# mini_shirasu.net
KiCad netlist of a schematic drawn in EAGLE
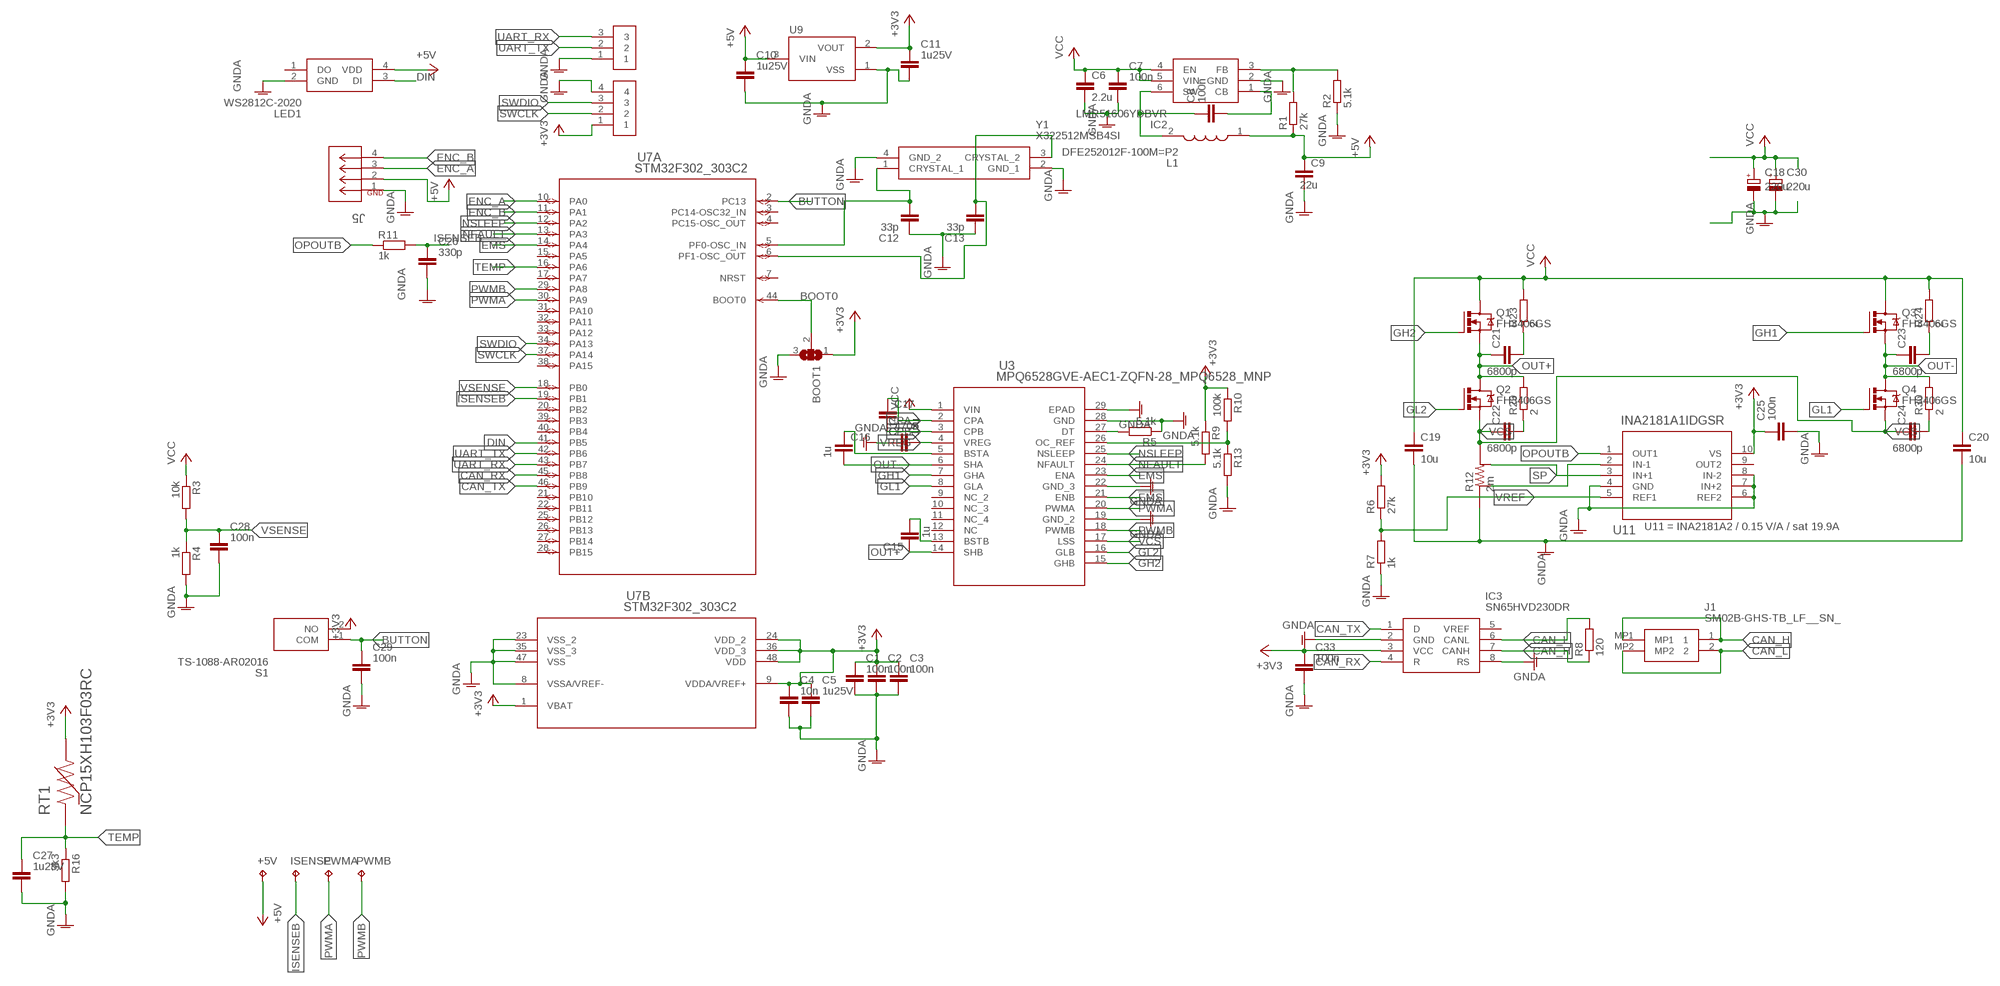
[diagram p0: schematic, sheet 1, part 1 of 2]
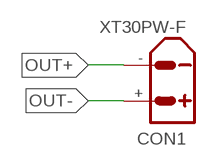
[diagram p1: schematic, sheet 1, part 2 of 2]

(export (version "E")
  (design (tool "Eeschema 10.0.6"))
  (components
    (comp (ref "+5V")
      (value "TPB1,27")
      (footprint "eagle-import:B1,27")
      (libsource (lib "eagle-import") (part "TPB1,27"))
    )
    (comp (ref "BOOT1")
      (value "SJ2W")
      (footprint "eagle-import:SJ_2")
      (libsource (lib "eagle-import") (part "SJ2W"))
    )
    (comp (ref "C1")
      (value "100n")
      (footprint "eagle-import:CAPC1005X60")
      (libsource (lib "eagle-import") (part "CCHIP-0402(1005-METRIC)_"))
    )
    (comp (ref "C2")
      (value "100n")
      (footprint "eagle-import:CAPC1005X60")
      (libsource (lib "eagle-import") (part "CCHIP-0402(1005-METRIC)_"))
    )
    (comp (ref "C3")
      (value "100n")
      (footprint "eagle-import:CAPC1005X60")
      (libsource (lib "eagle-import") (part "CCHIP-0402(1005-METRIC)_"))
    )
    (comp (ref "C4")
      (value "10n")
      (footprint "eagle-import:CAPC1005X60")
      (libsource (lib "eagle-import") (part "CCHIP-0402(1005-METRIC)_"))
    )
    (comp (ref "C5")
      (value "1u25V")
      (footprint "eagle-import:CAPC1005X60")
      (libsource (lib "eagle-import") (part "CCHIP-0402(1005-METRIC)_"))
    )
    (comp (ref "C6")
      (value "2.2u")
      (footprint "eagle-import:C0805")
      (libsource (lib "eagle-import") (part "C-EUC0805"))
    )
    (comp (ref "C7")
      (value "100n")
      (footprint "eagle-import:CAPC1005X60")
      (libsource (lib "eagle-import") (part "CCHIP-0402(1005-METRIC)_"))
    )
    (comp (ref "C8")
      (value "100n")
      (footprint "eagle-import:CAPC1005X60")
      (libsource (lib "eagle-import") (part "CCHIP-0402(1005-METRIC)_"))
    )
    (comp (ref "C9")
      (value "22u")
      (footprint "eagle-import:C0805")
      (libsource (lib "eagle-import") (part "C-EUC0805"))
    )
    (comp (ref "C10")
      (value "1u25V")
      (footprint "eagle-import:CAPC1005X60")
      (libsource (lib "eagle-import") (part "CCHIP-0402(1005-METRIC)_"))
    )
    (comp (ref "C11")
      (value "1u25V")
      (footprint "eagle-import:CAPC1005X60")
      (libsource (lib "eagle-import") (part "CCHIP-0402(1005-METRIC)_"))
    )
    (comp (ref "C12")
      (value "33p")
      (footprint "eagle-import:CAPC1005X60")
      (libsource (lib "eagle-import") (part "CCHIP-0402(1005-METRIC)_"))
    )
    (comp (ref "C13")
      (value "33p")
      (footprint "eagle-import:CAPC1005X60")
      (libsource (lib "eagle-import") (part "CCHIP-0402(1005-METRIC)_"))
    )
    (comp (ref "C14")
      (value "10u")
      (footprint "eagle-import:C0805")
      (libsource (lib "eagle-import") (part "C-EUC0805"))
    )
    (comp (ref "C15")
      (value "1u")
      (footprint "eagle-import:C0603")
      (libsource (lib "eagle-import") (part "C-EUC0603"))
    )
    (comp (ref "C16")
      (value "1u")
      (footprint "eagle-import:C0603")
      (libsource (lib "eagle-import") (part "C-EUC0603"))
    )
    (comp (ref "C17")
      (value "470n")
      (footprint "eagle-import:C0805")
      (libsource (lib "eagle-import") (part "C-EUC0805"))
    )
    (comp (ref "C18")
      (value "220u")
      (footprint "eagle-import:CAPAE1030X1050N")
      (libsource (lib "eagle-import") (part "C-POLECAP-10.5MM_"))
    )
    (comp (ref "C19")
      (value "10u")
      (footprint "eagle-import:C0805")
      (libsource (lib "eagle-import") (part "C-EUC0805"))
    )
    (comp (ref "C20")
      (value "10u")
      (footprint "eagle-import:C0805")
      (libsource (lib "eagle-import") (part "C-EUC0805"))
    )
    (comp (ref "C21")
      (value "6800p")
      (footprint "eagle-import:C0603")
      (libsource (lib "eagle-import") (part "C-EUC0603"))
    )
    (comp (ref "C22")
      (value "6800p")
      (footprint "eagle-import:C0603")
      (libsource (lib "eagle-import") (part "C-EUC0603"))
    )
    (comp (ref "C23")
      (value "6800p")
      (footprint "eagle-import:C0603")
      (libsource (lib "eagle-import") (part "C-EUC0603"))
    )
    (comp (ref "C24")
      (value "6800p")
      (footprint "eagle-import:C0603")
      (libsource (lib "eagle-import") (part "C-EUC0603"))
    )
    (comp (ref "C25")
      (value "100n")
      (footprint "eagle-import:CAPC1005X60")
      (libsource (lib "eagle-import") (part "CCHIP-0402(1005-METRIC)_"))
    )
    (comp (ref "C26")
      (value "330p")
      (footprint "eagle-import:CAPC1005X60")
      (libsource (lib "eagle-import") (part "CCHIP-0402(1005-METRIC)_"))
    )
    (comp (ref "C27")
      (value "1u25V")
      (footprint "eagle-import:CAPC1005X60")
      (libsource (lib "eagle-import") (part "CCHIP-0402(1005-METRIC)_"))
    )
    (comp (ref "C28")
      (value "100n")
      (footprint "eagle-import:CAPC1005X60")
      (libsource (lib "eagle-import") (part "CCHIP-0402(1005-METRIC)_"))
    )
    (comp (ref "C29")
      (value "100n")
      (footprint "eagle-import:CAPC1005X60")
      (libsource (lib "eagle-import") (part "CCHIP-0402(1005-METRIC)_"))
    )
    (comp (ref "C30")
      (value "220u")
      (footprint "eagle-import:CAPAE1030X1050N")
      (libsource (lib "eagle-import") (part "C-POLECAP-10.5MM_"))
    )
    (comp (ref "C33")
      (value "100n")
      (footprint "eagle-import:CAPC1005X60")
      (libsource (lib "eagle-import") (part "CCHIP-0402(1005-METRIC)_"))
    )
    (comp (ref "CON1")
      (value "XT30PW-F")
      (footprint "eagle-import:XT30PW-F")
      (libsource (lib "eagle-import") (part "XT30PW-F"))
    )
    (comp (ref "IC2")
      (value "LMR51606YDBVR")
      (footprint "eagle-import:SOT95P280X145-6N")
      (fields (field (name "MOUSER_PART_NUMBER") "595-LMR51606YDBVR"))
      (libsource (lib "eagle-import") (part "LMR51606YDBVR"))
    )
    (comp (ref "IC3")
      (value "SN65HVD230DR")
      (footprint "eagle-import:SOT127P600X175-8N")
      (fields (field (name "MOUSER_PART_NUMBER") "595-SN65HVD230DR"))
      (libsource (lib "eagle-import") (part "SN65HVD230DR"))
    )
    (comp (ref "ISENSE")
      (value "TPB1,27")
      (footprint "eagle-import:B1,27")
      (libsource (lib "eagle-import") (part "TPB1,27"))
    )
    (comp (ref "J1")
      (value "SM02B-GHS-TB_LF__SN_")
      (footprint "eagle-import:SM02BGHSTBLFSN")
      (fields (field (name "MANUFACTURER") "JST") (field (name "MPN") "SM02B-GHS-TB(LF)(SN)"))
      (libsource (lib "eagle-import") (part "SM02B-GHS-TB_LF__SN_"))
    )
    (comp (ref "J5")
      (value "EP2.5-4-SIDE")
      (footprint "eagle-import:CONN4_1744426-4")
      (fields (field (name "MANUFACTURER_PART_NUMBER") "17444264"))
      (libsource (lib "eagle-import") (part "EP2.5-4-SIDE"))
    )
    (comp (ref "L1")
      (value "DFE252012F-100M=P2")
      (footprint "eagle-import:DFE2HCAH1R0MJ0L")
      (fields (field (name "MOUSER_PART_NUMBER") "81-DFE252012F-100MP2"))
      (libsource (lib "eagle-import") (part "DFE252012F-100M=P2"))
    )
    (comp (ref "LED1")
      (value "WS2812C-2020")
      (footprint "eagle-import:WS2812C2020")
      (libsource (lib "eagle-import") (part "WS2812C-2020"))
    )
    (comp (ref "PWMA")
      (value "TPB1,27")
      (footprint "eagle-import:B1,27")
      (libsource (lib "eagle-import") (part "TPB1,27"))
    )
    (comp (ref "PWMB")
      (value "TPB1,27")
      (footprint "eagle-import:B1,27")
      (libsource (lib "eagle-import") (part "TPB1,27"))
    )
    (comp (ref "Q1")
      (value "FH3406GS")
      (footprint "eagle-import:DFN-8-5X6-FH3406GS")
      (libsource (lib "eagle-import") (part "FH3406GS"))
    )
    (comp (ref "Q2")
      (value "FH3406GS")
      (footprint "eagle-import:DFN-8-5X6-FH3406GS")
      (libsource (lib "eagle-import") (part "FH3406GS"))
    )
    (comp (ref "Q3")
      (value "FH3406GS")
      (footprint "eagle-import:DFN-8-5X6-FH3406GS")
      (libsource (lib "eagle-import") (part "FH3406GS"))
    )
    (comp (ref "Q4")
      (value "FH3406GS")
      (footprint "eagle-import:DFN-8-5X6-FH3406GS")
      (libsource (lib "eagle-import") (part "FH3406GS"))
    )
    (comp (ref "R1")
      (value "27k")
      (footprint "eagle-import:R0402")
      (libsource (lib "eagle-import") (part "R-EU_R0402"))
    )
    (comp (ref "R2")
      (value "5.1k")
      (footprint "eagle-import:R0402")
      (libsource (lib "eagle-import") (part "R-EU_R0402"))
    )
    (comp (ref "R3")
      (value "10k")
      (footprint "eagle-import:R0402")
      (libsource (lib "eagle-import") (part "R-EU_R0402"))
    )
    (comp (ref "R4")
      (value "1k")
      (footprint "eagle-import:R0402")
      (libsource (lib "eagle-import") (part "R-EU_R0402"))
    )
    (comp (ref "R5")
      (value "5.1k")
      (footprint "eagle-import:R0402")
      (libsource (lib "eagle-import") (part "R-EU_R0402"))
    )
    (comp (ref "R6")
      (value "27k")
      (footprint "eagle-import:R0402")
      (libsource (lib "eagle-import") (part "R-EU_R0402"))
    )
    (comp (ref "R7")
      (value "1k")
      (footprint "eagle-import:R0402")
      (libsource (lib "eagle-import") (part "R-EU_R0402"))
    )
    (comp (ref "R8")
      (value "120")
      (footprint "eagle-import:R0603")
      (libsource (lib "eagle-import") (part "R-EU_R0603"))
    )
    (comp (ref "R9")
      (value "5.1k")
      (footprint "eagle-import:R0402")
      (libsource (lib "eagle-import") (part "R-EU_R0402"))
    )
    (comp (ref "R10")
      (value "100k")
      (footprint "eagle-import:R0402")
      (libsource (lib "eagle-import") (part "R-EU_R0402"))
    )
    (comp (ref "R11")
      (value "1k")
      (footprint "eagle-import:R0402")
      (libsource (lib "eagle-import") (part "R-EU_R0402"))
    )
    (comp (ref "R12")
      (value "2m")
      (footprint "eagle-import:2512-4PAD")
      (libsource (lib "eagle-import") (part "R2512"))
    )
    (comp (ref "R13")
      (value "5.1k")
      (footprint "eagle-import:R0402")
      (libsource (lib "eagle-import") (part "R-EU_R0402"))
    )
    (comp (ref "R16")
      (value "3k3")
      (footprint "eagle-import:R0402")
      (libsource (lib "eagle-import") (part "R-EU_R0402"))
    )
    (comp (ref "R23")
      (value "2")
      (footprint "eagle-import:R0603")
      (libsource (lib "eagle-import") (part "R-EU_R0603"))
    )
    (comp (ref "R24")
      (value "2")
      (footprint "eagle-import:R0603")
      (libsource (lib "eagle-import") (part "R-EU_R0603"))
    )
    (comp (ref "R29")
      (value "2")
      (footprint "eagle-import:R0603")
      (libsource (lib "eagle-import") (part "R-EU_R0603"))
    )
    (comp (ref "R30")
      (value "2")
      (footprint "eagle-import:R0603")
      (libsource (lib "eagle-import") (part "R-EU_R0603"))
    )
    (comp (ref "RT1")
      (value "NCP15XH103F03RC")
      (footprint "eagle-import:THRMC1005X55N")
      (fields (field (name "MF") "Murata"))
      (libsource (lib "eagle-import") (part "NCP15XH103F03RC"))
    )
    (comp (ref "S1")
      (value "TS-1088-AR02016")
      (footprint "eagle-import:TS1088AR02016")
      (libsource (lib "eagle-import") (part "TS-1088-AR02016"))
    )
    (comp (ref "U$1")
      (value "PIN_HEADERPIN_HEADER")
      (footprint "eagle-import:PIN_HEADER")
      (libsource (lib "eagle-import") (part "PIN_HEADERPIN_HEADER"))
    )
    (comp (ref "U$2")
      (value "3PIN_HEADER")
      (footprint "eagle-import:3PIN_HEADER")
      (libsource (lib "eagle-import") (part "3PIN_HEADER"))
    )
    (comp (ref "U3")
      (value "MPQ6528GVE-AEC1-ZQFN-28_MPQ6528_MNP")
      (footprint "eagle-import:QFN-28_MPQ6528_MNP")
      (fields
        (field (name "MANUFACTURER_PART_NUMBER") "MPQ6528GVE-AEC1-Z")
        (field (name "COPYRIGHT") "Copyright (C) 2026 Ultra Librarian. All rights reserved.")
      )
      (libsource (lib "eagle-import") (part "MPQ6528GVE-AEC1-ZQFN-28_MPQ6528_MNP"))
    )
    (comp (ref "U7")
      (value "STM32F302_303C2")
      (footprint "eagle-import:LQFP48-7X7MM")
      (fields (field (name "COPYRIGHT") "Copyright (C) 2016 Accelerated Designs. All rights reserved"))
      (libsource (lib "eagle-import") (part "STM32F302_303C2"))
    )
    (comp (ref "U9")
      (value "XC6206")
      (footprint "eagle-import:SOT95P240X110-3")
      (libsource (lib "eagle-import") (part "XC6206"))
    )
    (comp (ref "U11")
      (value "INA2181A1IDGSR")
      (footprint "eagle-import:DGS10")
      (fields
        (field (name "MANUFACTURER_PART_NUMBER") "INA2181A2IDGSR")
        (field (name "COPYRIGHT") "Copyright (C) 2018 Accelerated Designs. All rights reserved")
      )
      (libsource (lib "eagle-import") (part "INA2181A1IDGSR"))
    )
    (comp (ref "Y1")
      (value "X322512MSB4SI")
      (footprint "eagle-import:X322512MSB4SI")
      (libsource (lib "eagle-import") (part "X322512MSB4SI"))
    )
  )
  (nets
    (net (code "1") (name "+3V3") (class "Default")
      (node (ref "BOOT1") (pin "1") (pinfunction "1_1") (pintype "passive"))
      (node (ref "C1") (pin "1") (pinfunction "1_1") (pintype "passive"))
      (node (ref "C11") (pin "1") (pinfunction "1_1") (pintype "passive"))
      (node (ref "C2") (pin "1") (pinfunction "1_1") (pintype "passive"))
      (node (ref "C25") (pin "1") (pinfunction "1_1") (pintype "passive"))
      (node (ref "C3") (pin "1") (pinfunction "1_1") (pintype "passive"))
      (node (ref "C33") (pin "1") (pinfunction "1_1") (pintype "passive"))
      (node (ref "C4") (pin "1") (pinfunction "1_1") (pintype "passive"))
      (node (ref "C5") (pin "1") (pinfunction "1_1") (pintype "passive"))
      (node (ref "IC3") (pin "3") (pinfunction "VCC_3") (pintype "bidirectional"))
      (node (ref "R10") (pin "1") (pinfunction "1_1") (pintype "passive"))
      (node (ref "R6") (pin "2") (pinfunction "2_2") (pintype "passive"))
      (node (ref "R9") (pin "1") (pinfunction "1_1") (pintype "passive"))
      (node (ref "RT1") (pin "2") (pinfunction "2_2") (pintype "passive"))
      (node (ref "S1") (pin "2") (pinfunction "NO_2") (pintype "bidirectional"))
      (node (ref "U$1") (pin "1") (pinfunction "1_1") (pintype "bidirectional"))
      (node (ref "U11") (pin "10") (pinfunction "VS_10") (pintype "power_in"))
      (node (ref "U7") (pin "1") (pinfunction "VBAT_1") (pintype "power_in"))
      (node (ref "U7") (pin "24") (pinfunction "VDD_2_24") (pintype "power_in"))
      (node (ref "U7") (pin "36") (pinfunction "VDD_3_36") (pintype "power_in"))
      (node (ref "U7") (pin "48") (pinfunction "VDD_48") (pintype "power_in"))
      (node (ref "U7") (pin "9") (pinfunction "VDDA/VREF+_9") (pintype "power_in"))
      (node (ref "U9") (pin "2") (pinfunction "VOUT_2") (pintype "bidirectional"))
    )
    (net (code "2") (name "+5V") (class "Default")
      (node (ref "+5V") (pin "TP") (pinfunction "TP_TP") (pintype "input"))
      (node (ref "C10") (pin "1") (pinfunction "1_1") (pintype "passive"))
      (node (ref "C9") (pin "1") (pinfunction "1_1") (pintype "passive"))
      (node (ref "J5") (pin "2") (pinfunction "2_2") (pintype "passive"))
      (node (ref "L1") (pin "1") (pinfunction "1_1") (pintype "bidirectional"))
      (node (ref "LED1") (pin "4") (pinfunction "VDD_4") (pintype "bidirectional"))
      (node (ref "R1") (pin "1") (pinfunction "1_1") (pintype "passive"))
      (node (ref "U9") (pin "3") (pinfunction "VIN_3") (pintype "bidirectional"))
    )
    (net (code "3") (name "/BOOT0") (class "Default")
      (node (ref "BOOT1") (pin "2") (pinfunction "2_2") (pintype "passive"))
      (node (ref "U7") (pin "44") (pinfunction "BOOT0_44") (pintype "input"))
    )
    (net (code "4") (name "/~{EMS}") (class "Default")
      (node (ref "U3") (pin "21") (pinfunction "ENB_21") (pintype "power_in"))
      (node (ref "U3") (pin "23") (pinfunction "ENA_23") (pintype "passive"))
      (node (ref "U7") (pin "14") (pinfunction "PA4_14") (pintype "bidirectional"))
    )
    (net (code "5") (name "BUTTON") (class "Default")
      (node (ref "C29") (pin "1") (pinfunction "1_1") (pintype "passive"))
      (node (ref "S1") (pin "1") (pinfunction "COM_1") (pintype "bidirectional"))
      (node (ref "U7") (pin "2") (pinfunction "PC13_2") (pintype "bidirectional"))
    )
    (net (code "6") (name "CAN_H") (class "Default")
      (node (ref "IC3") (pin "7") (pinfunction "CANH_7") (pintype "bidirectional"))
      (node (ref "J1") (pin "1") (pinfunction "1_1") (pintype "bidirectional"))
      (node (ref "J1") (pin "MP1") (pinfunction "MP1_MP1") (pintype "bidirectional"))
      (node (ref "R8") (pin "1") (pinfunction "1_1") (pintype "passive"))
    )
    (net (code "7") (name "CAN_L") (class "Default")
      (node (ref "IC3") (pin "6") (pinfunction "CANL_6") (pintype "bidirectional"))
      (node (ref "J1") (pin "2") (pinfunction "2_2") (pintype "bidirectional"))
      (node (ref "J1") (pin "MP2") (pinfunction "MP2_MP2") (pintype "bidirectional"))
      (node (ref "R8") (pin "2") (pinfunction "2_2") (pintype "passive"))
    )
    (net (code "8") (name "CAN_RX") (class "Default")
      (node (ref "IC3") (pin "4") (pinfunction "R_4") (pintype "bidirectional"))
      (node (ref "U7") (pin "45") (pinfunction "PB8_45") (pintype "bidirectional"))
    )
    (net (code "9") (name "CAN_TX") (class "Default")
      (node (ref "IC3") (pin "1") (pinfunction "D_1") (pintype "bidirectional"))
      (node (ref "U7") (pin "46") (pinfunction "PB9_46") (pintype "bidirectional"))
    )
    (net (code "10") (name "CPA") (class "Default")
      (node (ref "C17") (pin "1") (pinfunction "1_1") (pintype "passive"))
      (node (ref "U3") (pin "2") (pinfunction "CPA_2") (pintype "passive"))
    )
    (net (code "11") (name "CPB") (class "Default")
      (node (ref "C17") (pin "2") (pinfunction "2_2") (pintype "passive"))
      (node (ref "U3") (pin "3") (pinfunction "CPB_3") (pintype "passive"))
    )
    (net (code "12") (name "DIN") (class "Default")
      (node (ref "LED1") (pin "3") (pinfunction "DI_3") (pintype "bidirectional"))
      (node (ref "U7") (pin "41") (pinfunction "PB5_41") (pintype "bidirectional"))
    )
    (net (code "13") (name "ENC_A") (class "Default")
      (node (ref "J5") (pin "3") (pinfunction "3_3") (pintype "passive"))
      (node (ref "U7") (pin "10") (pinfunction "PA0_10") (pintype "bidirectional"))
    )
    (net (code "14") (name "ENC_B") (class "Default")
      (node (ref "J5") (pin "4") (pinfunction "4_4") (pintype "passive"))
      (node (ref "U7") (pin "11") (pinfunction "PA1_11") (pintype "bidirectional"))
    )
    (net (code "15") (name "GH1") (class "Default")
      (node (ref "Q3") (pin "4") (pinfunction "G_4") (pintype "passive"))
      (node (ref "U3") (pin "7") (pinfunction "GHA_7") (pintype "passive"))
    )
    (net (code "16") (name "GH2") (class "Default")
      (node (ref "Q1") (pin "4") (pinfunction "G_4") (pintype "passive"))
      (node (ref "U3") (pin "15") (pinfunction "GHB_15") (pintype "passive"))
    )
    (net (code "17") (name "GL1") (class "Default")
      (node (ref "Q4") (pin "4") (pinfunction "G_4") (pintype "passive"))
      (node (ref "U3") (pin "8") (pinfunction "GLA_8") (pintype "passive"))
    )
    (net (code "18") (name "GL2") (class "Default")
      (node (ref "Q2") (pin "4") (pinfunction "G_4") (pintype "passive"))
      (node (ref "U3") (pin "16") (pinfunction "GLB_16") (pintype "passive"))
    )
    (net (code "19") (name "GNDA") (class "Default")
      (node (ref "BOOT1") (pin "3") (pinfunction "3_3") (pintype "passive"))
      (node (ref "C1") (pin "2") (pinfunction "2_2") (pintype "passive"))
      (node (ref "C10") (pin "2") (pinfunction "2_2") (pintype "passive"))
      (node (ref "C11") (pin "2") (pinfunction "2_2") (pintype "passive"))
      (node (ref "C12") (pin "1") (pinfunction "1_1") (pintype "passive"))
      (node (ref "C13") (pin "1") (pinfunction "1_1") (pintype "passive"))
      (node (ref "C14") (pin "1") (pinfunction "1_1") (pintype "passive"))
      (node (ref "C18") (pin "2") (pinfunction "-_2") (pintype "passive"))
      (node (ref "C19") (pin "2") (pinfunction "2_2") (pintype "passive"))
      (node (ref "C2") (pin "2") (pinfunction "2_2") (pintype "passive"))
      (node (ref "C20") (pin "2") (pinfunction "2_2") (pintype "passive"))
      (node (ref "C25") (pin "2") (pinfunction "2_2") (pintype "passive"))
      (node (ref "C26") (pin "2") (pinfunction "2_2") (pintype "passive"))
      (node (ref "C27") (pin "2") (pinfunction "2_2") (pintype "passive"))
      (node (ref "C28") (pin "2") (pinfunction "2_2") (pintype "passive"))
      (node (ref "C29") (pin "2") (pinfunction "2_2") (pintype "passive"))
      (node (ref "C3") (pin "2") (pinfunction "2_2") (pintype "passive"))
      (node (ref "C30") (pin "2") (pinfunction "-_2") (pintype "passive"))
      (node (ref "C33") (pin "2") (pinfunction "2_2") (pintype "passive"))
      (node (ref "C4") (pin "2") (pinfunction "2_2") (pintype "passive"))
      (node (ref "C5") (pin "2") (pinfunction "2_2") (pintype "passive"))
      (node (ref "C6") (pin "2") (pinfunction "2_2") (pintype "passive"))
      (node (ref "C7") (pin "2") (pinfunction "2_2") (pintype "passive"))
      (node (ref "C9") (pin "2") (pinfunction "2_2") (pintype "passive"))
      (node (ref "IC2") (pin "2") (pinfunction "GND_2") (pintype "bidirectional"))
      (node (ref "IC3") (pin "2") (pinfunction "GND_2") (pintype "bidirectional"))
      (node (ref "IC3") (pin "8") (pinfunction "RS_8") (pintype "bidirectional"))
      (node (ref "J5") (pin "1") (pinfunction "1_1") (pintype "passive"))
      (node (ref "LED1") (pin "2") (pinfunction "GND_2") (pintype "bidirectional"))
      (node (ref "R12") (pin "1") (pinfunction "1_1") (pintype "passive"))
      (node (ref "R12") (pin "2") (pinfunction "1_2") (pintype "passive"))
      (node (ref "R13") (pin "2") (pinfunction "2_2") (pintype "passive"))
      (node (ref "R16") (pin "2") (pinfunction "2_2") (pintype "passive"))
      (node (ref "R2") (pin "1") (pinfunction "1_1") (pintype "passive"))
      (node (ref "R4") (pin "2") (pinfunction "2_2") (pintype "passive"))
      (node (ref "R5") (pin "1") (pinfunction "1_1") (pintype "passive"))
      (node (ref "R7") (pin "1") (pinfunction "1_1") (pintype "passive"))
      (node (ref "U$1") (pin "4") (pinfunction "4_4") (pintype "bidirectional"))
      (node (ref "U$2") (pin "1") (pinfunction "1_1") (pintype "bidirectional"))
      (node (ref "U11") (pin "4") (pinfunction "GND_4") (pintype "power_in"))
      (node (ref "U11") (pin "6") (pinfunction "REF2_6") (pintype "input"))
      (node (ref "U11") (pin "7") (pinfunction "IN+2_7") (pintype "input"))
      (node (ref "U11") (pin "8") (pinfunction "IN-2_8") (pintype "input"))
      (node (ref "U3") (pin "19") (pinfunction "GND_2_19") (pintype "power_in"))
      (node (ref "U3") (pin "22") (pinfunction "GND_3_22") (pintype "passive"))
      (node (ref "U3") (pin "28") (pinfunction "GND_28") (pintype "power_in"))
      (node (ref "U3") (pin "29") (pinfunction "EPAD_29") (pintype "power_in"))
      (node (ref "U7") (pin "23") (pinfunction "VSS_2_23") (pintype "power_in"))
      (node (ref "U7") (pin "35") (pinfunction "VSS_3_35") (pintype "power_in"))
      (node (ref "U7") (pin "47") (pinfunction "VSS_47") (pintype "power_in"))
      (node (ref "U7") (pin "8") (pinfunction "VSSA/VREF-_8") (pintype "power_in"))
      (node (ref "U9") (pin "1") (pinfunction "VSS_1") (pintype "bidirectional"))
      (node (ref "Y1") (pin "2") (pinfunction "GND_1_2") (pintype "bidirectional"))
      (node (ref "Y1") (pin "4") (pinfunction "GND_2_4") (pintype "bidirectional"))
    )
    (net (code "20") (name "ISENSEB") (class "Default")
      (node (ref "C26") (pin "1") (pinfunction "1_1") (pintype "passive"))
      (node (ref "ISENSE") (pin "TP") (pinfunction "TP_TP") (pintype "input"))
      (node (ref "R11") (pin "2") (pinfunction "2_2") (pintype "passive"))
      (node (ref "U7") (pin "19") (pinfunction "PB1_19") (pintype "bidirectional"))
    )
    (net (code "21") (name "NFAULT") (class "Default")
      (node (ref "R9") (pin "2") (pinfunction "2_2") (pintype "passive"))
      (node (ref "U3") (pin "24") (pinfunction "NFAULT_24") (pintype "output"))
      (node (ref "U7") (pin "13") (pinfunction "PA3_13") (pintype "bidirectional"))
    )
    (net (code "22") (name "NSLEEP") (class "Default")
      (node (ref "U3") (pin "25") (pinfunction "NSLEEP_25") (pintype "input"))
      (node (ref "U7") (pin "12") (pinfunction "PA2_12") (pintype "bidirectional"))
    )
    (net (code "23") (name "Net-(C21-Pad2)") (class "Default")
      (node (ref "C21") (pin "2") (pinfunction "2_2") (pintype "passive"))
      (node (ref "R23") (pin "1") (pinfunction "1_1") (pintype "passive"))
    )
    (net (code "24") (name "Net-(C22-Pad2)") (class "Default")
      (node (ref "C22") (pin "2") (pinfunction "2_2") (pintype "passive"))
      (node (ref "R29") (pin "1") (pinfunction "1_1") (pintype "passive"))
    )
    (net (code "25") (name "Net-(C23-Pad2)") (class "Default")
      (node (ref "C23") (pin "2") (pinfunction "2_2") (pintype "passive"))
      (node (ref "R24") (pin "1") (pinfunction "1_1") (pintype "passive"))
    )
    (net (code "26") (name "Net-(C24-Pad2)") (class "Default")
      (node (ref "C24") (pin "2") (pinfunction "2_2") (pintype "passive"))
      (node (ref "R30") (pin "1") (pinfunction "1_1") (pintype "passive"))
    )
    (net (code "27") (name "Net-(IC2-CB)") (class "Default")
      (node (ref "C8") (pin "2") (pinfunction "2_2") (pintype "passive"))
      (node (ref "IC2") (pin "1") (pinfunction "CB_1") (pintype "bidirectional"))
    )
    (net (code "28") (name "Net-(IC2-FB)") (class "Default")
      (node (ref "IC2") (pin "3") (pinfunction "FB_3") (pintype "bidirectional"))
      (node (ref "R1") (pin "2") (pinfunction "2_2") (pintype "passive"))
      (node (ref "R2") (pin "2") (pinfunction "2_2") (pintype "passive"))
    )
    (net (code "29") (name "Net-(IC2-SW)") (class "Default")
      (node (ref "C8") (pin "1") (pinfunction "1_1") (pintype "passive"))
      (node (ref "IC2") (pin "6") (pinfunction "SW_6") (pintype "bidirectional"))
      (node (ref "L1") (pin "2") (pinfunction "2_2") (pintype "bidirectional"))
    )
    (net (code "30") (name "Net-(R12-3)") (class "Default")
      (node (ref "R12") (pin "5") (pinfunction "3_5") (pintype "bidirectional"))
      (node (ref "U11") (pin "2") (pinfunction "IN-1_2") (pintype "input"))
    )
    (net (code "31") (name "Net-(U3-BSTA)") (class "Default")
      (node (ref "C16") (pin "1") (pinfunction "1_1") (pintype "passive"))
      (node (ref "U3") (pin "5") (pinfunction "BSTA_5") (pintype "passive"))
    )
    (net (code "32") (name "Net-(U3-BSTB)") (class "Default")
      (node (ref "C15") (pin "2") (pinfunction "2_2") (pintype "passive"))
      (node (ref "U3") (pin "13") (pinfunction "BSTB_13") (pintype "passive"))
    )
    (net (code "33") (name "Net-(U3-DT)") (class "Default")
      (node (ref "R5") (pin "2") (pinfunction "2_2") (pintype "passive"))
      (node (ref "U3") (pin "27") (pinfunction "DT_27") (pintype "passive"))
    )
    (net (code "34") (name "Net-(U3-OC_REF)") (class "Default")
      (node (ref "R10") (pin "2") (pinfunction "2_2") (pintype "passive"))
      (node (ref "R13") (pin "1") (pinfunction "1_1") (pintype "passive"))
      (node (ref "U3") (pin "26") (pinfunction "OC_REF_26") (pintype "input"))
    )
    (net (code "35") (name "Net-(U7A-PF0-OSC_IN)") (class "Default")
      (node (ref "C12") (pin "2") (pinfunction "2_2") (pintype "passive"))
      (node (ref "U7") (pin "5") (pinfunction "PF0-OSC_IN_5") (pintype "bidirectional"))
      (node (ref "Y1") (pin "1") (pinfunction "CRYSTAL_1_1") (pintype "bidirectional"))
    )
    (net (code "36") (name "Net-(U7A-PF1-OSC_OUT)") (class "Default")
      (node (ref "C13") (pin "2") (pinfunction "2_2") (pintype "passive"))
      (node (ref "U7") (pin "6") (pinfunction "PF1-OSC_OUT_6") (pintype "bidirectional"))
      (node (ref "Y1") (pin "3") (pinfunction "CRYSTAL_2_3") (pintype "bidirectional"))
    )
    (net (code "37") (name "OPOUTB") (class "Default")
      (node (ref "R11") (pin "1") (pinfunction "1_1") (pintype "passive"))
      (node (ref "U11") (pin "1") (pinfunction "OUT1_1") (pintype "output"))
    )
    (net (code "38") (name "OUT+") (class "Default")
      (node (ref "C15") (pin "1") (pinfunction "1_1") (pintype "passive"))
      (node (ref "C21") (pin "1") (pinfunction "1_1") (pintype "passive"))
      (node (ref "CON1") (pin "-") (pinfunction "-_-") (pintype "power_in"))
      (node (ref "Q1") (pin "1") (pinfunction "S_1") (pintype "passive"))
      (node (ref "Q1") (pin "2") (pinfunction "S_2") (pintype "passive"))
      (node (ref "Q1") (pin "3") (pinfunction "S_3") (pintype "passive"))
      (node (ref "Q2") (pin "5") (pinfunction "D_5") (pintype "passive"))
      (node (ref "Q2") (pin "6") (pinfunction "D_6") (pintype "passive"))
      (node (ref "Q2") (pin "7") (pinfunction "D_7") (pintype "passive"))
      (node (ref "Q2") (pin "8") (pinfunction "D_8") (pintype "passive"))
      (node (ref "Q2") (pin "9") (pinfunction "D_9") (pintype "passive"))
      (node (ref "R29") (pin "2") (pinfunction "2_2") (pintype "passive"))
      (node (ref "U3") (pin "14") (pinfunction "SHB_14") (pintype "passive"))
    )
    (net (code "39") (name "OUT-") (class "Default")
      (node (ref "C16") (pin "2") (pinfunction "2_2") (pintype "passive"))
      (node (ref "C23") (pin "1") (pinfunction "1_1") (pintype "passive"))
      (node (ref "CON1") (pin "+") (pinfunction "+_+") (pintype "power_in"))
      (node (ref "Q3") (pin "1") (pinfunction "S_1") (pintype "passive"))
      (node (ref "Q3") (pin "2") (pinfunction "S_2") (pintype "passive"))
      (node (ref "Q3") (pin "3") (pinfunction "S_3") (pintype "passive"))
      (node (ref "Q4") (pin "5") (pinfunction "D_5") (pintype "passive"))
      (node (ref "Q4") (pin "6") (pinfunction "D_6") (pintype "passive"))
      (node (ref "Q4") (pin "7") (pinfunction "D_7") (pintype "passive"))
      (node (ref "Q4") (pin "8") (pinfunction "D_8") (pintype "passive"))
      (node (ref "Q4") (pin "9") (pinfunction "D_9") (pintype "passive"))
      (node (ref "R30") (pin "2") (pinfunction "2_2") (pintype "passive"))
      (node (ref "U3") (pin "6") (pinfunction "SHA_6") (pintype "passive"))
    )
    (net (code "40") (name "PWMA") (class "Default")
      (node (ref "PWMA") (pin "TP") (pinfunction "TP_TP") (pintype "input"))
      (node (ref "U3") (pin "20") (pinfunction "PWMA_20") (pintype "input"))
      (node (ref "U7") (pin "30") (pinfunction "PA9_30") (pintype "bidirectional"))
    )
    (net (code "41") (name "PWMB") (class "Default")
      (node (ref "PWMB") (pin "TP") (pinfunction "TP_TP") (pintype "input"))
      (node (ref "U3") (pin "18") (pinfunction "PWMB_18") (pintype "input"))
      (node (ref "U7") (pin "29") (pinfunction "PA8_29") (pintype "bidirectional"))
    )
    (net (code "42") (name "SP") (class "Default")
      (node (ref "R12") (pin "6") (pinfunction "4_6") (pintype "bidirectional"))
      (node (ref "U11") (pin "3") (pinfunction "IN+1_3") (pintype "input"))
    )
    (net (code "43") (name "SWCLK") (class "Default")
      (node (ref "U$1") (pin "2") (pinfunction "2_2") (pintype "bidirectional"))
      (node (ref "U7") (pin "37") (pinfunction "PA14_37") (pintype "bidirectional"))
    )
    (net (code "44") (name "SWDIO") (class "Default")
      (node (ref "U$1") (pin "3") (pinfunction "3_3") (pintype "bidirectional"))
      (node (ref "U7") (pin "34") (pinfunction "PA13_34") (pintype "bidirectional"))
    )
    (net (code "45") (name "TEMP") (class "Default")
      (node (ref "C27") (pin "1") (pinfunction "1_1") (pintype "passive"))
      (node (ref "R16") (pin "1") (pinfunction "1_1") (pintype "passive"))
      (node (ref "RT1") (pin "1") (pinfunction "1_1") (pintype "passive"))
      (node (ref "U7") (pin "16") (pinfunction "PA6_16") (pintype "bidirectional"))
    )
    (net (code "46") (name "UART_RX") (class "Default")
      (node (ref "U$2") (pin "3") (pinfunction "3_3") (pintype "bidirectional"))
      (node (ref "U7") (pin "43") (pinfunction "PB7_43") (pintype "bidirectional"))
    )
    (net (code "47") (name "UART_TX") (class "Default")
      (node (ref "U$2") (pin "2") (pinfunction "2_2") (pintype "bidirectional"))
      (node (ref "U7") (pin "42") (pinfunction "PB6_42") (pintype "bidirectional"))
    )
    (net (code "48") (name "VCC") (class "Default")
      (node (ref "C18") (pin "1") (pinfunction "+_1") (pintype "passive"))
      (node (ref "C19") (pin "1") (pinfunction "1_1") (pintype "passive"))
      (node (ref "C20") (pin "1") (pinfunction "1_1") (pintype "passive"))
      (node (ref "C30") (pin "1") (pinfunction "+_1") (pintype "passive"))
      (node (ref "C6") (pin "1") (pinfunction "1_1") (pintype "passive"))
      (node (ref "C7") (pin "1") (pinfunction "1_1") (pintype "passive"))
      (node (ref "IC2") (pin "4") (pinfunction "EN_4") (pintype "bidirectional"))
      (node (ref "IC2") (pin "5") (pinfunction "VIN_5") (pintype "bidirectional"))
      (node (ref "Q1") (pin "5") (pinfunction "D_5") (pintype "passive"))
      (node (ref "Q1") (pin "6") (pinfunction "D_6") (pintype "passive"))
      (node (ref "Q1") (pin "7") (pinfunction "D_7") (pintype "passive"))
      (node (ref "Q1") (pin "8") (pinfunction "D_8") (pintype "passive"))
      (node (ref "Q1") (pin "9") (pinfunction "D_9") (pintype "passive"))
      (node (ref "Q3") (pin "5") (pinfunction "D_5") (pintype "passive"))
      (node (ref "Q3") (pin "6") (pinfunction "D_6") (pintype "passive"))
      (node (ref "Q3") (pin "7") (pinfunction "D_7") (pintype "passive"))
      (node (ref "Q3") (pin "8") (pinfunction "D_8") (pintype "passive"))
      (node (ref "Q3") (pin "9") (pinfunction "D_9") (pintype "passive"))
      (node (ref "R23") (pin "2") (pinfunction "2_2") (pintype "passive"))
      (node (ref "R24") (pin "2") (pinfunction "2_2") (pintype "passive"))
      (node (ref "R3") (pin "1") (pinfunction "1_1") (pintype "passive"))
      (node (ref "U3") (pin "1") (pinfunction "VIN_1") (pintype "power_in"))
    )
    (net (code "49") (name "VCS") (class "Default")
      (node (ref "C22") (pin "1") (pinfunction "1_1") (pintype "passive"))
      (node (ref "C24") (pin "1") (pinfunction "1_1") (pintype "passive"))
      (node (ref "Q2") (pin "1") (pinfunction "S_1") (pintype "passive"))
      (node (ref "Q2") (pin "2") (pinfunction "S_2") (pintype "passive"))
      (node (ref "Q2") (pin "3") (pinfunction "S_3") (pintype "passive"))
      (node (ref "Q4") (pin "1") (pinfunction "S_1") (pintype "passive"))
      (node (ref "Q4") (pin "2") (pinfunction "S_2") (pintype "passive"))
      (node (ref "Q4") (pin "3") (pinfunction "S_3") (pintype "passive"))
      (node (ref "R12") (pin "3") (pinfunction "2_3") (pintype "passive"))
      (node (ref "R12") (pin "4") (pinfunction "2_4") (pintype "passive"))
      (node (ref "U3") (pin "17") (pinfunction "LSS_17") (pintype "passive"))
    )
    (net (code "50") (name "VREF") (class "Default")
      (node (ref "R6") (pin "1") (pinfunction "1_1") (pintype "passive"))
      (node (ref "R7") (pin "2") (pinfunction "2_2") (pintype "passive"))
      (node (ref "U11") (pin "5") (pinfunction "REF1_5") (pintype "input"))
    )
    (net (code "51") (name "VREG") (class "Default")
      (node (ref "C14") (pin "2") (pinfunction "2_2") (pintype "passive"))
      (node (ref "U3") (pin "4") (pinfunction "VREG_4") (pintype "output"))
    )
    (net (code "52") (name "VSENSE") (class "Default")
      (node (ref "C28") (pin "1") (pinfunction "1_1") (pintype "passive"))
      (node (ref "R3") (pin "2") (pinfunction "2_2") (pintype "passive"))
      (node (ref "R4") (pin "1") (pinfunction "1_1") (pintype "passive"))
      (node (ref "U7") (pin "18") (pinfunction "PB0_18") (pintype "bidirectional"))
    )
    (net (code "53") (name "unconnected-(IC3-VREF-Pad5)") (class "Default")
      (node (ref "IC3") (pin "5") (pinfunction "VREF_5") (pintype "bidirectional"))
    )
    (net (code "54") (name "unconnected-(LED1-DO-Pad1)") (class "Default")
      (node (ref "LED1") (pin "1") (pinfunction "DO_1") (pintype "bidirectional"))
    )
    (net (code "55") (name "unconnected-(U3-NC-Pad12)") (class "Default")
      (node (ref "U3") (pin "12") (pinfunction "NC_12") (pintype "no_connect"))
    )
    (net (code "56") (name "unconnected-(U3-NC_2-Pad9)") (class "Default")
      (node (ref "U3") (pin "9") (pinfunction "NC_2_9") (pintype "no_connect"))
    )
    (net (code "57") (name "unconnected-(U3-NC_3-Pad10)") (class "Default")
      (node (ref "U3") (pin "10") (pinfunction "NC_3_10") (pintype "no_connect"))
    )
    (net (code "58") (name "unconnected-(U3-NC_4-Pad11)") (class "Default")
      (node (ref "U3") (pin "11") (pinfunction "NC_4_11") (pintype "no_connect"))
    )
    (net (code "59") (name "unconnected-(U7A-NRST-Pad7)") (class "Default")
      (node (ref "U7") (pin "7") (pinfunction "NRST_7") (pintype "bidirectional"))
    )
    (net (code "60") (name "unconnected-(U7A-PA5-Pad15)") (class "Default")
      (node (ref "U7") (pin "15") (pinfunction "PA5_15") (pintype "bidirectional"))
    )
    (net (code "61") (name "unconnected-(U7A-PA7-Pad17)") (class "Default")
      (node (ref "U7") (pin "17") (pinfunction "PA7_17") (pintype "bidirectional"))
    )
    (net (code "62") (name "unconnected-(U7A-PA10-Pad31)") (class "Default")
      (node (ref "U7") (pin "31") (pinfunction "PA10_31") (pintype "bidirectional"))
    )
    (net (code "63") (name "unconnected-(U7A-PA11-Pad32)") (class "Default")
      (node (ref "U7") (pin "32") (pinfunction "PA11_32") (pintype "bidirectional"))
    )
    (net (code "64") (name "unconnected-(U7A-PA12-Pad33)") (class "Default")
      (node (ref "U7") (pin "33") (pinfunction "PA12_33") (pintype "bidirectional"))
    )
    (net (code "65") (name "unconnected-(U7A-PA15-Pad38)") (class "Default")
      (node (ref "U7") (pin "38") (pinfunction "PA15_38") (pintype "bidirectional"))
    )
    (net (code "66") (name "unconnected-(U7A-PB2-Pad20)") (class "Default")
      (node (ref "U7") (pin "20") (pinfunction "PB2_20") (pintype "bidirectional"))
    )
    (net (code "67") (name "unconnected-(U7A-PB3-Pad39)") (class "Default")
      (node (ref "U7") (pin "39") (pinfunction "PB3_39") (pintype "bidirectional"))
    )
    (net (code "68") (name "unconnected-(U7A-PB4-Pad40)") (class "Default")
      (node (ref "U7") (pin "40") (pinfunction "PB4_40") (pintype "bidirectional"))
    )
    (net (code "69") (name "unconnected-(U7A-PB10-Pad21)") (class "Default")
      (node (ref "U7") (pin "21") (pinfunction "PB10_21") (pintype "bidirectional"))
    )
    (net (code "70") (name "unconnected-(U7A-PB11-Pad22)") (class "Default")
      (node (ref "U7") (pin "22") (pinfunction "PB11_22") (pintype "bidirectional"))
    )
    (net (code "71") (name "unconnected-(U7A-PB12-Pad25)") (class "Default")
      (node (ref "U7") (pin "25") (pinfunction "PB12_25") (pintype "bidirectional"))
    )
    (net (code "72") (name "unconnected-(U7A-PB13-Pad26)") (class "Default")
      (node (ref "U7") (pin "26") (pinfunction "PB13_26") (pintype "bidirectional"))
    )
    (net (code "73") (name "unconnected-(U7A-PB14-Pad27)") (class "Default")
      (node (ref "U7") (pin "27") (pinfunction "PB14_27") (pintype "bidirectional"))
    )
    (net (code "74") (name "unconnected-(U7A-PB15-Pad28)") (class "Default")
      (node (ref "U7") (pin "28") (pinfunction "PB15_28") (pintype "bidirectional"))
    )
    (net (code "75") (name "unconnected-(U7A-PC14-OSC32_IN-Pad3)") (class "Default")
      (node (ref "U7") (pin "3") (pinfunction "PC14-OSC32_IN_3") (pintype "bidirectional"))
    )
    (net (code "76") (name "unconnected-(U7A-PC15-OSC_OUT-Pad4)") (class "Default")
      (node (ref "U7") (pin "4") (pinfunction "PC15-OSC_OUT_4") (pintype "bidirectional"))
    )
    (net (code "77") (name "unconnected-(U11-OUT2-Pad9)") (class "Default")
      (node (ref "U11") (pin "9") (pinfunction "OUT2_9") (pintype "output"))
    )
  )
)
